# CH4D3M0_Rev_1.net
KiCad netlist of a schematic drawn in EAGLE
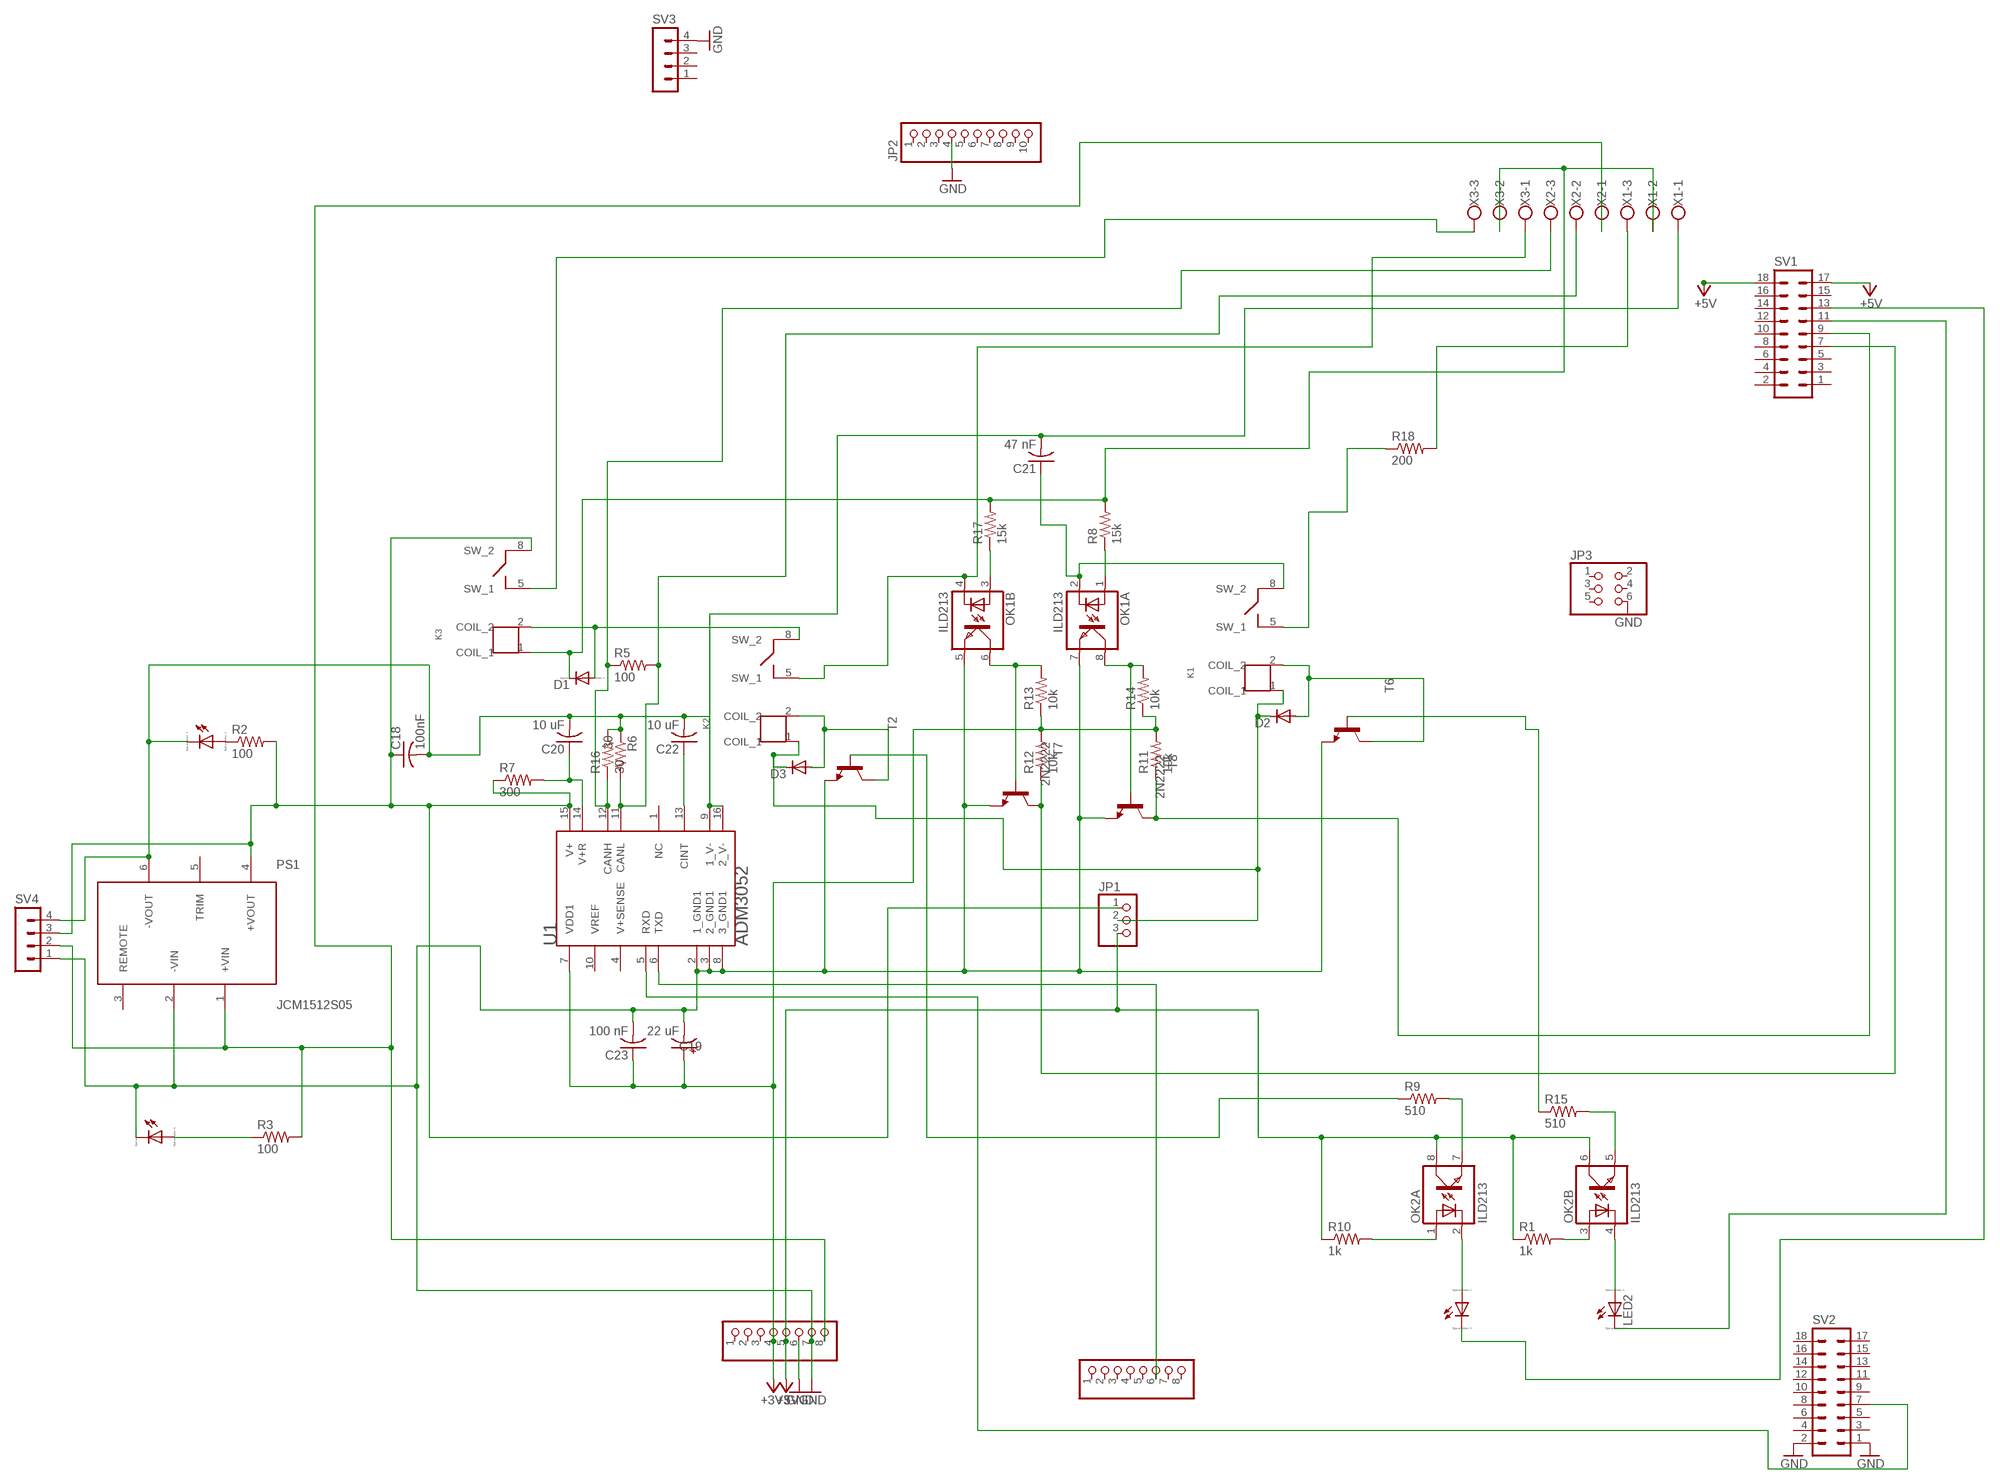
[diagram p0: schematic, sheet 1]

(export (version "E")
  (design (tool "Eeschema 10.0.6"))
  (components
    (comp (ref "ADCH")
      (value "PINHD-1X8")
      (footprint "eagle-import:1X08")
      (libsource (lib "eagle-import") (part "PINHD-1X8"))
    )
    (comp (ref "ADCH2")
      (value "PINHD-1X8")
      (footprint "eagle-import:1X08")
      (libsource (lib "eagle-import") (part "PINHD-1X8"))
    )
    (comp (ref "C18")
      (value "100nF")
      (footprint "eagle-import:C025-024X044")
      (libsource (lib "eagle-import") (part "C-US025-024X044"))
    )
    (comp (ref "C19")
      (value "22 uF")
      (footprint "eagle-import:E2,5RE")
      (libsource (lib "eagle-import") (part "CPOL-USE2.5-4V"))
    )
    (comp (ref "C20")
      (value "10 uF")
      (footprint "eagle-import:C025-024X044")
      (libsource (lib "eagle-import") (part "C-US025-024X044"))
    )
    (comp (ref "C21")
      (value "47 nF")
      (footprint "eagle-import:C025-024X044")
      (libsource (lib "eagle-import") (part "C-US025-024X044"))
    )
    (comp (ref "C22")
      (value "10 uF")
      (footprint "eagle-import:C025-024X044")
      (libsource (lib "eagle-import") (part "C-US025-024X044"))
    )
    (comp (ref "C23")
      (value "100 nF")
      (footprint "eagle-import:C025-024X044")
      (libsource (lib "eagle-import") (part "C-US025-024X044"))
    )
    (comp (ref "D1")
      (value "DIODE-D-5")
      (footprint "eagle-import:D-5")
      (libsource (lib "eagle-import") (part "DIODE-D-5"))
    )
    (comp (ref "D2")
      (value "DIODE-D-5")
      (footprint "eagle-import:D-5")
      (libsource (lib "eagle-import") (part "DIODE-D-5"))
    )
    (comp (ref "D3")
      (value "DIODE-D-5")
      (footprint "eagle-import:D-5")
      (libsource (lib "eagle-import") (part "DIODE-D-5"))
    )
    (comp (ref "JP1")
      (value "PINHD-1X3")
      (footprint "eagle-import:1X03")
      (libsource (lib "eagle-import") (part "PINHD-1X3"))
    )
    (comp (ref "JP2")
      (value "PINHD-1X10")
      (footprint "eagle-import:1X10")
      (libsource (lib "eagle-import") (part "PINHD-1X10"))
    )
    (comp (ref "JP3")
      (value "PINHD-2X3")
      (footprint "eagle-import:2X03")
      (libsource (lib "eagle-import") (part "PINHD-2X3"))
    )
    (comp (ref "K1")
      (value "G6DN-1ATHROUGH_HOLE")
      (footprint "eagle-import:G6DN-1A")
      (libsource (lib "eagle-import") (part "G6DN-1ATHROUGH_HOLE"))
    )
    (comp (ref "K2")
      (value "G6DN-1ATHROUGH_HOLE")
      (footprint "eagle-import:G6DN-1A")
      (libsource (lib "eagle-import") (part "G6DN-1ATHROUGH_HOLE"))
    )
    (comp (ref "K3")
      (value "G6DN-1ATHROUGH_HOLE")
      (footprint "eagle-import:G6DN-1A")
      (libsource (lib "eagle-import") (part "G6DN-1ATHROUGH_HOLE"))
    )
    (comp (ref "LED1")
      (value "LED_ELD260")
      (footprint "eagle-import:LED_LD260")
      (libsource (lib "eagle-import") (part "LED_ELD260"))
    )
    (comp (ref "LED2")
      (value "LED_ELD260")
      (footprint "eagle-import:LED_LD260")
      (libsource (lib "eagle-import") (part "LED_ELD260"))
    )
    (comp (ref "LED3")
      (value "LED_ELD260")
      (footprint "eagle-import:LED_LD260")
      (libsource (lib "eagle-import") (part "LED_ELD260"))
    )
    (comp (ref "LED4")
      (value "LED_ELD260")
      (footprint "eagle-import:LED_LD260")
      (libsource (lib "eagle-import") (part "LED_ELD260"))
    )
    (comp (ref "OK1")
      (value "ILD213")
      (footprint "eagle-import:SOIC08")
      (fields (field (name "MF") "VISHAY/TELEFUNKEN") (field (name "MPN") "ILD213T"))
      (libsource (lib "eagle-import") (part "ILD213"))
    )
    (comp (ref "OK2")
      (value "ILD213")
      (footprint "eagle-import:SOIC08")
      (fields (field (name "MF") "VISHAY/TELEFUNKEN") (field (name "MPN") "ILD213T"))
      (libsource (lib "eagle-import") (part "ILD213"))
    )
    (comp (ref "PS1")
      (value "JCM1512S05")
      (footprint "eagle-import:JCMXX")
      (libsource (lib "eagle-import") (part "JCMXXTHROUGH_HOLE"))
    )
    (comp (ref "R1")
      (value "1k")
      (footprint "eagle-import:0204_7")
      (libsource (lib "eagle-import") (part "R-US_0204/7"))
    )
    (comp (ref "R2")
      (value "100")
      (footprint "eagle-import:0204_7")
      (libsource (lib "eagle-import") (part "R-US_0204/7"))
    )
    (comp (ref "R3")
      (value "100")
      (footprint "eagle-import:0204_7")
      (libsource (lib "eagle-import") (part "R-US_0204/7"))
    )
    (comp (ref "R5")
      (value "100")
      (footprint "eagle-import:0204_7")
      (libsource (lib "eagle-import") (part "R-US_0204/7"))
    )
    (comp (ref "R6")
      (value "30")
      (footprint "eagle-import:0204_7")
      (libsource (lib "eagle-import") (part "R-US_0204/7"))
    )
    (comp (ref "R7")
      (value "300")
      (footprint "eagle-import:0204_7")
      (libsource (lib "eagle-import") (part "R-US_0204/7"))
    )
    (comp (ref "R8")
      (value "15k")
      (footprint "eagle-import:0204_7")
      (libsource (lib "eagle-import") (part "R-US_0204/7"))
    )
    (comp (ref "R9")
      (value "510")
      (footprint "eagle-import:0204_7")
      (libsource (lib "eagle-import") (part "R-US_0204/7"))
    )
    (comp (ref "R10")
      (value "1k")
      (footprint "eagle-import:0204_7")
      (libsource (lib "eagle-import") (part "R-US_0204/7"))
    )
    (comp (ref "R11")
      (value "10k")
      (footprint "eagle-import:0204_7")
      (libsource (lib "eagle-import") (part "R-US_0204/7"))
    )
    (comp (ref "R12")
      (value "10k")
      (footprint "eagle-import:0204_7")
      (libsource (lib "eagle-import") (part "R-US_0204/7"))
    )
    (comp (ref "R13")
      (value "10k")
      (footprint "eagle-import:0204_7")
      (libsource (lib "eagle-import") (part "R-US_0204/7"))
    )
    (comp (ref "R14")
      (value "10k")
      (footprint "eagle-import:0204_7")
      (libsource (lib "eagle-import") (part "R-US_0204/7"))
    )
    (comp (ref "R15")
      (value "510")
      (footprint "eagle-import:0204_7")
      (libsource (lib "eagle-import") (part "R-US_0204/7"))
    )
    (comp (ref "R16")
      (value "30")
      (footprint "eagle-import:0204_7")
      (libsource (lib "eagle-import") (part "R-US_0204/7"))
    )
    (comp (ref "R17")
      (value "15k")
      (footprint "eagle-import:0204_7")
      (libsource (lib "eagle-import") (part "R-US_0204/7"))
    )
    (comp (ref "R18")
      (value "200")
      (footprint "eagle-import:0204_7")
      (libsource (lib "eagle-import") (part "R-US_0204/7"))
    )
    (comp (ref "SV1")
      (value "MA09-2")
      (footprint "eagle-import:MA09-2")
      (libsource (lib "eagle-import") (part "MA09-2"))
    )
    (comp (ref "SV2")
      (value "MA09-2")
      (footprint "eagle-import:MA09-2")
      (libsource (lib "eagle-import") (part "MA09-2"))
    )
    (comp (ref "SV3")
      (value "MA04-1")
      (footprint "eagle-import:MA04-1")
      (libsource (lib "eagle-import") (part "MA04-1"))
    )
    (comp (ref "SV4")
      (value "MA04-1")
      (footprint "eagle-import:MA04-1")
      (libsource (lib "eagle-import") (part "MA04-1"))
    )
    (comp (ref "T2")
      (value "BC547-NPN-TO92-CBE")
      (footprint "eagle-import:TO92-CBE")
      (libsource (lib "eagle-import") (part "-NPN-TO92-CBEBC547"))
    )
    (comp (ref "T6")
      (value "BC547-NPN-TO92-CBE")
      (footprint "eagle-import:TO92-CBE")
      (libsource (lib "eagle-import") (part "-NPN-TO92-CBEBC547"))
    )
    (comp (ref "T7")
      (value "2N2222")
      (footprint "eagle-import:TO92-EBC-OVAL")
      (libsource (lib "eagle-import") (part "2N2222"))
    )
    (comp (ref "T8")
      (value "2N2222")
      (footprint "eagle-import:TO92-EBC-OVAL")
      (libsource (lib "eagle-import") (part "2N2222"))
    )
    (comp (ref "U1")
      (value "ANALOG_DEVICES_INC_ADM3052ANALOG_DEVICES_INC_ADM3052_0_0")
      (footprint "eagle-import:ANALOG_DEVICES_INC_ADM3052_0")
      (fields
        (field (name "DIGIKEY_PART_NUMBER") "ADM3052BRWZ-REEL7")
        (field (name "MF") "Analog Devices Inc")
        (field (name "MOUSER_PART_NUMBER") "584-ADM3052BRWZ-R7")
      )
      (libsource (lib "eagle-import") (part "ANALOG_DEVICES_INC_ADM3052ANALOG_DEVICES_INC_ADM3052_0_0"))
    )
    (comp (ref "X1")
      (value "W237-103")
      (footprint "eagle-import:W237-103")
      (fields (field (name "MPN") "237-103"))
      (libsource (lib "eagle-import") (part "W237-103"))
    )
    (comp (ref "X2")
      (value "W237-103")
      (footprint "eagle-import:W237-103")
      (fields (field (name "MPN") "237-103"))
      (libsource (lib "eagle-import") (part "W237-103"))
    )
    (comp (ref "X3")
      (value "W237-103")
      (footprint "eagle-import:W237-103")
      (fields (field (name "MPN") "237-103"))
      (libsource (lib "eagle-import") (part "W237-103"))
    )
  )
  (nets
    (net (code "1") (name "+3V3") (class "Default")
      (node (ref "ADCH2") (pin "4") (pinfunction "4_4") (pintype "passive"))
      (node (ref "C19") (pin "+") (pinfunction "+_+") (pintype "passive"))
      (node (ref "C23") (pin "1") (pinfunction "1_1") (pintype "passive"))
      (node (ref "R11") (pin "2") (pinfunction "2_2") (pintype "passive"))
      (node (ref "R12") (pin "2") (pinfunction "2_2") (pintype "passive"))
      (node (ref "R13") (pin "1") (pinfunction "1_1") (pintype "passive"))
      (node (ref "R14") (pin "1") (pinfunction "1_1") (pintype "passive"))
      (node (ref "U1") (pin "7") (pinfunction "VDD1_7") (pintype "bidirectional"))
    )
    (net (code "2") (name "+5V") (class "Default")
      (node (ref "ADCH2") (pin "5") (pinfunction "5_5") (pintype "passive"))
      (node (ref "JP1") (pin "3") (pinfunction "3_3") (pintype "passive"))
      (node (ref "OK2") (pin "6") (pinfunction "COL_6") (pintype "passive"))
      (node (ref "OK2") (pin "8") (pinfunction "COL_8") (pintype "passive"))
      (node (ref "R1") (pin "1") (pinfunction "1_1") (pintype "passive"))
      (node (ref "R10") (pin "1") (pinfunction "1_1") (pintype "passive"))
      (node (ref "SV1") (pin "17") (pinfunction "17_17") (pintype "passive"))
      (node (ref "SV1") (pin "18") (pinfunction "18_18") (pintype "passive"))
    )
    (net (code "3") (name "GND") (class "Default")
      (node (ref "ADCH2") (pin "6") (pinfunction "6_6") (pintype "passive"))
      (node (ref "ADCH2") (pin "7") (pinfunction "7_7") (pintype "passive"))
      (node (ref "C19") (pin "-") (pinfunction "-_-") (pintype "passive"))
      (node (ref "C23") (pin "2") (pinfunction "2_2") (pintype "passive"))
      (node (ref "JP2") (pin "4") (pinfunction "4_4") (pintype "passive"))
      (node (ref "JP3") (pin "6") (pinfunction "6_6") (pintype "passive"))
      (node (ref "LED4") (pin "K") (pinfunction "C_K") (pintype "passive"))
      (node (ref "OK1") (pin "5") (pinfunction "EMIT_5") (pintype "passive"))
      (node (ref "OK1") (pin "7") (pinfunction "EMIT_7") (pintype "passive"))
      (node (ref "PS1") (pin "2") (pinfunction "-VIN_2") (pintype "power_in"))
      (node (ref "SV2") (pin "1") (pinfunction "1_1") (pintype "passive"))
      (node (ref "SV2") (pin "2") (pinfunction "2_2") (pintype "passive"))
      (node (ref "SV3") (pin "4") (pinfunction "4_4") (pintype "passive"))
      (node (ref "SV4") (pin "1") (pinfunction "1_1") (pintype "passive"))
      (node (ref "T2") (pin "E") (pinfunction "E_E") (pintype "passive"))
      (node (ref "T6") (pin "E") (pinfunction "E_E") (pintype "passive"))
      (node (ref "T7") (pin "E") (pinfunction "E_E") (pintype "passive"))
      (node (ref "T8") (pin "E") (pinfunction "E_E") (pintype "passive"))
      (node (ref "U1") (pin "2") (pinfunction "1_GND1_2") (pintype "bidirectional"))
      (node (ref "U1") (pin "3") (pinfunction "2_GND1_3") (pintype "bidirectional"))
      (node (ref "U1") (pin "8") (pinfunction "3_GND1_8") (pintype "bidirectional"))
    )
    (net (code "4") (name "Net-(K1-COIL_1)") (class "Default")
      (node (ref "D2") (pin "C") (pinfunction "C_C") (pintype "passive"))
      (node (ref "D3") (pin "C") (pinfunction "C_C") (pintype "passive"))
      (node (ref "JP1") (pin "2") (pinfunction "2_2") (pintype "passive"))
      (node (ref "K1") (pin "1") (pinfunction "COIL_1_1") (pintype "bidirectional"))
      (node (ref "K2") (pin "1") (pinfunction "COIL_1_1") (pintype "bidirectional"))
    )
    (net (code "5") (name "Net-(K1-COIL_2)") (class "Default")
      (node (ref "D2") (pin "A") (pinfunction "A_A") (pintype "passive"))
      (node (ref "K1") (pin "2") (pinfunction "COIL_2_2") (pintype "bidirectional"))
      (node (ref "T6") (pin "C") (pinfunction "C_C") (pintype "passive"))
    )
    (net (code "6") (name "Net-(K1-SW_1)") (class "Default")
      (node (ref "K1") (pin "5") (pinfunction "SW_1_5") (pintype "bidirectional"))
      (node (ref "R18") (pin "1") (pinfunction "1_1") (pintype "passive"))
    )
    (net (code "7") (name "Net-(K1-SW_2)") (class "Default")
      (node (ref "C21") (pin "1") (pinfunction "1_1") (pintype "passive"))
      (node (ref "K1") (pin "8") (pinfunction "SW_2_8") (pintype "bidirectional"))
      (node (ref "OK1") (pin "2") (pinfunction "C_2") (pintype "passive"))
    )
    (net (code "8") (name "Net-(K2-COIL_2)") (class "Default")
      (node (ref "D3") (pin "A") (pinfunction "A_A") (pintype "passive"))
      (node (ref "K2") (pin "2") (pinfunction "COIL_2_2") (pintype "bidirectional"))
      (node (ref "T2") (pin "C") (pinfunction "C_C") (pintype "passive"))
    )
    (net (code "9") (name "Net-(K2-SW_1)") (class "Default")
      (node (ref "K2") (pin "5") (pinfunction "SW_1_5") (pintype "bidirectional"))
      (node (ref "OK1") (pin "4") (pinfunction "C_4") (pintype "passive"))
      (node (ref "X3") (pin "1") (pinfunction "KL_1") (pintype "passive"))
    )
    (net (code "10") (name "Net-(K2-SW_2)") (class "Default")
      (node (ref "D1") (pin "A") (pinfunction "A_A") (pintype "passive"))
      (node (ref "K2") (pin "8") (pinfunction "SW_2_8") (pintype "bidirectional"))
      (node (ref "K3") (pin "2") (pinfunction "COIL_2_2") (pintype "bidirectional"))
    )
    (net (code "11") (name "Net-(K3-COIL_1)") (class "Default")
      (node (ref "D1") (pin "C") (pinfunction "C_C") (pintype "passive"))
      (node (ref "K3") (pin "1") (pinfunction "COIL_1_1") (pintype "bidirectional"))
      (node (ref "R17") (pin "2") (pinfunction "2_2") (pintype "passive"))
      (node (ref "R8") (pin "2") (pinfunction "2_2") (pintype "passive"))
      (node (ref "X1") (pin "2") (pinfunction "KL_2") (pintype "passive"))
      (node (ref "X3") (pin "2") (pinfunction "KL_2") (pintype "passive"))
    )
    (net (code "12") (name "Net-(K3-SW_1)") (class "Default")
      (node (ref "K3") (pin "5") (pinfunction "SW_1_5") (pintype "bidirectional"))
      (node (ref "X3") (pin "3") (pinfunction "KL_3") (pintype "passive"))
    )
    (net (code "13") (name "Net-(K3-SW_2)") (class "Default")
      (node (ref "C18") (pin "1") (pinfunction "1_1") (pintype "passive"))
      (node (ref "JP1") (pin "1") (pinfunction "1_1") (pintype "passive"))
      (node (ref "K3") (pin "8") (pinfunction "SW_2_8") (pintype "bidirectional"))
      (node (ref "PS1") (pin "4") (pinfunction "+VOUT_4") (pintype "output"))
      (node (ref "R2") (pin "2") (pinfunction "2_2") (pintype "passive"))
      (node (ref "R7") (pin "1") (pinfunction "1_1") (pintype "passive"))
      (node (ref "SV4") (pin "3") (pinfunction "3_3") (pintype "passive"))
      (node (ref "U1") (pin "15") (pinfunction "V+_15") (pintype "bidirectional"))
    )
    (net (code "14") (name "Net-(LED1-C)") (class "Default")
      (node (ref "LED1") (pin "K") (pinfunction "C_K") (pintype "passive"))
      (node (ref "SV1") (pin "13") (pinfunction "13_13") (pintype "passive"))
    )
    (net (code "15") (name "Net-(LED2-C)") (class "Default")
      (node (ref "LED2") (pin "K") (pinfunction "C_K") (pintype "passive"))
      (node (ref "SV1") (pin "11") (pinfunction "11_11") (pintype "passive"))
    )
    (net (code "16") (name "Net-(LED3-C)") (class "Default")
      (node (ref "C18") (pin "2") (pinfunction "2_2") (pintype "passive"))
      (node (ref "C20") (pin "2") (pinfunction "2_2") (pintype "passive"))
      (node (ref "C21") (pin "2") (pinfunction "2_2") (pintype "passive"))
      (node (ref "C22") (pin "2") (pinfunction "2_2") (pintype "passive"))
      (node (ref "LED3") (pin "K") (pinfunction "C_K") (pintype "passive"))
      (node (ref "PS1") (pin "6") (pinfunction "-VOUT_6") (pintype "output"))
      (node (ref "R16") (pin "2") (pinfunction "2_2") (pintype "passive"))
      (node (ref "R6") (pin "1") (pinfunction "1_1") (pintype "passive"))
      (node (ref "SV4") (pin "4") (pinfunction "4_4") (pintype "passive"))
      (node (ref "U1") (pin "16") (pinfunction "2_V-_16") (pintype "bidirectional"))
      (node (ref "U1") (pin "9") (pinfunction "1_V-_9") (pintype "bidirectional"))
      (node (ref "X1") (pin "1") (pinfunction "KL_1") (pintype "passive"))
    )
    (net (code "17") (name "Net-(LED3-PadA)") (class "Default")
      (node (ref "LED3") (pin "A") (pinfunction "A_A") (pintype "passive"))
      (node (ref "R2") (pin "1") (pinfunction "1_1") (pintype "passive"))
    )
    (net (code "18") (name "Net-(LED4-PadA)") (class "Default")
      (node (ref "LED4") (pin "A") (pinfunction "A_A") (pintype "passive"))
      (node (ref "R3") (pin "1") (pinfunction "1_1") (pintype "passive"))
    )
    (net (code "19") (name "Net-(OK1A-A)") (class "Default")
      (node (ref "OK1") (pin "1") (pinfunction "A_1") (pintype "passive"))
      (node (ref "R8") (pin "1") (pinfunction "1_1") (pintype "passive"))
    )
    (net (code "20") (name "Net-(OK1A-COL)") (class "Default")
      (node (ref "OK1") (pin "8") (pinfunction "COL_8") (pintype "passive"))
      (node (ref "R14") (pin "2") (pinfunction "2_2") (pintype "passive"))
      (node (ref "T8") (pin "B") (pinfunction "B_B") (pintype "passive"))
    )
    (net (code "21") (name "Net-(OK1B-A)") (class "Default")
      (node (ref "OK1") (pin "3") (pinfunction "A_3") (pintype "passive"))
      (node (ref "R17") (pin "1") (pinfunction "1_1") (pintype "passive"))
    )
    (net (code "22") (name "Net-(OK1B-COL)") (class "Default")
      (node (ref "OK1") (pin "6") (pinfunction "COL_6") (pintype "passive"))
      (node (ref "R13") (pin "2") (pinfunction "2_2") (pintype "passive"))
      (node (ref "T7") (pin "B") (pinfunction "B_B") (pintype "passive"))
    )
    (net (code "23") (name "Net-(OK2A-A)") (class "Default")
      (node (ref "OK2") (pin "1") (pinfunction "A_1") (pintype "passive"))
      (node (ref "R10") (pin "2") (pinfunction "2_2") (pintype "passive"))
    )
    (net (code "24") (name "Net-(OK2A-C)") (class "Default")
      (node (ref "LED1") (pin "A") (pinfunction "A_A") (pintype "passive"))
      (node (ref "OK2") (pin "2") (pinfunction "C_2") (pintype "passive"))
    )
    (net (code "25") (name "Net-(OK2A-EMIT)") (class "Default")
      (node (ref "OK2") (pin "7") (pinfunction "EMIT_7") (pintype "passive"))
      (node (ref "R9") (pin "2") (pinfunction "2_2") (pintype "passive"))
    )
    (net (code "26") (name "Net-(OK2B-A)") (class "Default")
      (node (ref "OK2") (pin "3") (pinfunction "A_3") (pintype "passive"))
      (node (ref "R1") (pin "2") (pinfunction "2_2") (pintype "passive"))
    )
    (net (code "27") (name "Net-(OK2B-C)") (class "Default")
      (node (ref "LED2") (pin "A") (pinfunction "A_A") (pintype "passive"))
      (node (ref "OK2") (pin "4") (pinfunction "C_4") (pintype "passive"))
    )
    (net (code "28") (name "Net-(OK2B-EMIT)") (class "Default")
      (node (ref "OK2") (pin "5") (pinfunction "EMIT_5") (pintype "passive"))
      (node (ref "R15") (pin "2") (pinfunction "2_2") (pintype "passive"))
    )
    (net (code "29") (name "Net-(PS1-+VIN)") (class "Default")
      (node (ref "ADCH2") (pin "8") (pinfunction "8_8") (pintype "passive"))
      (node (ref "PS1") (pin "1") (pinfunction "+VIN_1") (pintype "power_in"))
      (node (ref "R3") (pin "2") (pinfunction "2_2") (pintype "passive"))
      (node (ref "SV4") (pin "2") (pinfunction "2_2") (pintype "passive"))
      (node (ref "X2") (pin "1") (pinfunction "KL_1") (pintype "passive"))
    )
    (net (code "30") (name "Net-(R9-Pad1)") (class "Default")
      (node (ref "R9") (pin "1") (pinfunction "1_1") (pintype "passive"))
      (node (ref "T2") (pin "B") (pinfunction "B_B") (pintype "passive"))
    )
    (net (code "31") (name "Net-(R11-Pad1)") (class "Default")
      (node (ref "R11") (pin "1") (pinfunction "1_1") (pintype "passive"))
      (node (ref "SV1") (pin "9") (pinfunction "9_9") (pintype "passive"))
      (node (ref "T8") (pin "C") (pinfunction "C_C") (pintype "passive"))
    )
    (net (code "32") (name "Net-(R12-Pad1)") (class "Default")
      (node (ref "R12") (pin "1") (pinfunction "1_1") (pintype "passive"))
      (node (ref "SV1") (pin "7") (pinfunction "7_7") (pintype "passive"))
      (node (ref "T7") (pin "C") (pinfunction "C_C") (pintype "passive"))
    )
    (net (code "33") (name "Net-(R15-Pad1)") (class "Default")
      (node (ref "R15") (pin "1") (pinfunction "1_1") (pintype "passive"))
      (node (ref "T6") (pin "B") (pinfunction "B_B") (pintype "passive"))
    )
    (net (code "34") (name "Net-(U1-CANH)") (class "Default")
      (node (ref "R16") (pin "1") (pinfunction "1_1") (pintype "passive"))
      (node (ref "R5") (pin "1") (pinfunction "1_1") (pintype "passive"))
      (node (ref "U1") (pin "12") (pinfunction "CANH_12") (pintype "bidirectional"))
      (node (ref "X2") (pin "3") (pinfunction "KL_3") (pintype "passive"))
    )
    (net (code "35") (name "Net-(U1-CANL)") (class "Default")
      (node (ref "R5") (pin "2") (pinfunction "2_2") (pintype "passive"))
      (node (ref "R6") (pin "2") (pinfunction "2_2") (pintype "passive"))
      (node (ref "U1") (pin "11") (pinfunction "CANL_11") (pintype "bidirectional"))
      (node (ref "X2") (pin "2") (pinfunction "KL_2") (pintype "passive"))
    )
    (net (code "36") (name "Net-(U1-CINT)") (class "Default")
      (node (ref "C22") (pin "1") (pinfunction "1_1") (pintype "passive"))
      (node (ref "U1") (pin "13") (pinfunction "CINT_13") (pintype "bidirectional"))
    )
    (net (code "37") (name "Net-(U1-RXD)") (class "Default")
      (node (ref "SV2") (pin "7") (pinfunction "7_7") (pintype "passive"))
      (node (ref "U1") (pin "5") (pinfunction "RXD_5") (pintype "bidirectional"))
    )
    (net (code "38") (name "Net-(U1-TXD)") (class "Default")
      (node (ref "ADCH") (pin "6") (pinfunction "6_6") (pintype "passive"))
      (node (ref "U1") (pin "6") (pinfunction "TXD_6") (pintype "bidirectional"))
    )
    (net (code "39") (name "Net-(U1-V+R)") (class "Default")
      (node (ref "C20") (pin "1") (pinfunction "1_1") (pintype "passive"))
      (node (ref "R7") (pin "2") (pinfunction "2_2") (pintype "passive"))
      (node (ref "U1") (pin "14") (pinfunction "V+R_14") (pintype "bidirectional"))
    )
    (net (code "40") (name "Net-(X1C-KL)") (class "Default")
      (node (ref "R18") (pin "2") (pinfunction "2_2") (pintype "passive"))
      (node (ref "X1") (pin "3") (pinfunction "KL_3") (pintype "passive"))
    )
    (net (code "41") (name "unconnected-(ADCH-Pad1)") (class "Default")
      (node (ref "ADCH") (pin "1") (pinfunction "1_1") (pintype "passive"))
    )
    (net (code "42") (name "unconnected-(ADCH-Pad2)") (class "Default")
      (node (ref "ADCH") (pin "2") (pinfunction "2_2") (pintype "passive"))
    )
    (net (code "43") (name "unconnected-(ADCH-Pad3)") (class "Default")
      (node (ref "ADCH") (pin "3") (pinfunction "3_3") (pintype "passive"))
    )
    (net (code "44") (name "unconnected-(ADCH-Pad4)") (class "Default")
      (node (ref "ADCH") (pin "4") (pinfunction "4_4") (pintype "passive"))
    )
    (net (code "45") (name "unconnected-(ADCH-Pad5)") (class "Default")
      (node (ref "ADCH") (pin "5") (pinfunction "5_5") (pintype "passive"))
    )
    (net (code "46") (name "unconnected-(ADCH-Pad7)") (class "Default")
      (node (ref "ADCH") (pin "7") (pinfunction "7_7") (pintype "passive"))
    )
    (net (code "47") (name "unconnected-(ADCH-Pad8)") (class "Default")
      (node (ref "ADCH") (pin "8") (pinfunction "8_8") (pintype "passive"))
    )
    (net (code "48") (name "unconnected-(ADCH2-Pad1)") (class "Default")
      (node (ref "ADCH2") (pin "1") (pinfunction "1_1") (pintype "passive"))
    )
    (net (code "49") (name "unconnected-(ADCH2-Pad2)") (class "Default")
      (node (ref "ADCH2") (pin "2") (pinfunction "2_2") (pintype "passive"))
    )
    (net (code "50") (name "unconnected-(ADCH2-Pad3)") (class "Default")
      (node (ref "ADCH2") (pin "3") (pinfunction "3_3") (pintype "passive"))
    )
    (net (code "51") (name "unconnected-(JP2-Pad1)") (class "Default")
      (node (ref "JP2") (pin "1") (pinfunction "1_1") (pintype "passive"))
    )
    (net (code "52") (name "unconnected-(JP2-Pad2)") (class "Default")
      (node (ref "JP2") (pin "2") (pinfunction "2_2") (pintype "passive"))
    )
    (net (code "53") (name "unconnected-(JP2-Pad3)") (class "Default")
      (node (ref "JP2") (pin "3") (pinfunction "3_3") (pintype "passive"))
    )
    (net (code "54") (name "unconnected-(JP2-Pad5)") (class "Default")
      (node (ref "JP2") (pin "5") (pinfunction "5_5") (pintype "passive"))
    )
    (net (code "55") (name "unconnected-(JP2-Pad6)") (class "Default")
      (node (ref "JP2") (pin "6") (pinfunction "6_6") (pintype "passive"))
    )
    (net (code "56") (name "unconnected-(JP2-Pad7)") (class "Default")
      (node (ref "JP2") (pin "7") (pinfunction "7_7") (pintype "passive"))
    )
    (net (code "57") (name "unconnected-(JP2-Pad8)") (class "Default")
      (node (ref "JP2") (pin "8") (pinfunction "8_8") (pintype "passive"))
    )
    (net (code "58") (name "unconnected-(JP2-Pad9)") (class "Default")
      (node (ref "JP2") (pin "9") (pinfunction "9_9") (pintype "passive"))
    )
    (net (code "59") (name "unconnected-(JP2-Pad10)") (class "Default")
      (node (ref "JP2") (pin "10") (pinfunction "10_10") (pintype "passive"))
    )
    (net (code "60") (name "unconnected-(JP3-Pad1)") (class "Default")
      (node (ref "JP3") (pin "1") (pinfunction "1_1") (pintype "passive"))
    )
    (net (code "61") (name "unconnected-(JP3-Pad2)") (class "Default")
      (node (ref "JP3") (pin "2") (pinfunction "2_2") (pintype "passive"))
    )
    (net (code "62") (name "unconnected-(JP3-Pad3)") (class "Default")
      (node (ref "JP3") (pin "3") (pinfunction "3_3") (pintype "passive"))
    )
    (net (code "63") (name "unconnected-(JP3-Pad4)") (class "Default")
      (node (ref "JP3") (pin "4") (pinfunction "4_4") (pintype "passive"))
    )
    (net (code "64") (name "unconnected-(JP3-Pad5)") (class "Default")
      (node (ref "JP3") (pin "5") (pinfunction "5_5") (pintype "passive"))
    )
    (net (code "65") (name "unconnected-(PS1-REMOTE-Pad3)") (class "Default")
      (node (ref "PS1") (pin "3") (pinfunction "REMOTE_3") (pintype "input"))
    )
    (net (code "66") (name "unconnected-(PS1-TRIM-Pad5)") (class "Default")
      (node (ref "PS1") (pin "5") (pinfunction "TRIM_5") (pintype "input"))
    )
    (net (code "67") (name "unconnected-(SV1-Pad1)") (class "Default")
      (node (ref "SV1") (pin "1") (pinfunction "1_1") (pintype "passive"))
    )
    (net (code "68") (name "unconnected-(SV1-Pad2)") (class "Default")
      (node (ref "SV1") (pin "2") (pinfunction "2_2") (pintype "passive"))
    )
    (net (code "69") (name "unconnected-(SV1-Pad3)") (class "Default")
      (node (ref "SV1") (pin "3") (pinfunction "3_3") (pintype "passive"))
    )
    (net (code "70") (name "unconnected-(SV1-Pad4)") (class "Default")
      (node (ref "SV1") (pin "4") (pinfunction "4_4") (pintype "passive"))
    )
    (net (code "71") (name "unconnected-(SV1-Pad5)") (class "Default")
      (node (ref "SV1") (pin "5") (pinfunction "5_5") (pintype "passive"))
    )
    (net (code "72") (name "unconnected-(SV1-Pad6)") (class "Default")
      (node (ref "SV1") (pin "6") (pinfunction "6_6") (pintype "passive"))
    )
    (net (code "73") (name "unconnected-(SV1-Pad8)") (class "Default")
      (node (ref "SV1") (pin "8") (pinfunction "8_8") (pintype "passive"))
    )
    (net (code "74") (name "unconnected-(SV1-Pad10)") (class "Default")
      (node (ref "SV1") (pin "10") (pinfunction "10_10") (pintype "passive"))
    )
    (net (code "75") (name "unconnected-(SV1-Pad12)") (class "Default")
      (node (ref "SV1") (pin "12") (pinfunction "12_12") (pintype "passive"))
    )
    (net (code "76") (name "unconnected-(SV1-Pad14)") (class "Default")
      (node (ref "SV1") (pin "14") (pinfunction "14_14") (pintype "passive"))
    )
    (net (code "77") (name "unconnected-(SV1-Pad15)") (class "Default")
      (node (ref "SV1") (pin "15") (pinfunction "15_15") (pintype "passive"))
    )
    (net (code "78") (name "unconnected-(SV1-Pad16)") (class "Default")
      (node (ref "SV1") (pin "16") (pinfunction "16_16") (pintype "passive"))
    )
    (net (code "79") (name "unconnected-(SV2-Pad3)") (class "Default")
      (node (ref "SV2") (pin "3") (pinfunction "3_3") (pintype "passive"))
    )
    (net (code "80") (name "unconnected-(SV2-Pad4)") (class "Default")
      (node (ref "SV2") (pin "4") (pinfunction "4_4") (pintype "passive"))
    )
    (net (code "81") (name "unconnected-(SV2-Pad5)") (class "Default")
      (node (ref "SV2") (pin "5") (pinfunction "5_5") (pintype "passive"))
    )
    (net (code "82") (name "unconnected-(SV2-Pad6)") (class "Default")
      (node (ref "SV2") (pin "6") (pinfunction "6_6") (pintype "passive"))
    )
    (net (code "83") (name "unconnected-(SV2-Pad8)") (class "Default")
      (node (ref "SV2") (pin "8") (pinfunction "8_8") (pintype "passive"))
    )
    (net (code "84") (name "unconnected-(SV2-Pad9)") (class "Default")
      (node (ref "SV2") (pin "9") (pinfunction "9_9") (pintype "passive"))
    )
    (net (code "85") (name "unconnected-(SV2-Pad10)") (class "Default")
      (node (ref "SV2") (pin "10") (pinfunction "10_10") (pintype "passive"))
    )
    (net (code "86") (name "unconnected-(SV2-Pad11)") (class "Default")
      (node (ref "SV2") (pin "11") (pinfunction "11_11") (pintype "passive"))
    )
    (net (code "87") (name "unconnected-(SV2-Pad12)") (class "Default")
      (node (ref "SV2") (pin "12") (pinfunction "12_12") (pintype "passive"))
    )
    (net (code "88") (name "unconnected-(SV2-Pad13)") (class "Default")
      (node (ref "SV2") (pin "13") (pinfunction "13_13") (pintype "passive"))
    )
    (net (code "89") (name "unconnected-(SV2-Pad14)") (class "Default")
      (node (ref "SV2") (pin "14") (pinfunction "14_14") (pintype "passive"))
    )
    (net (code "90") (name "unconnected-(SV2-Pad15)") (class "Default")
      (node (ref "SV2") (pin "15") (pinfunction "15_15") (pintype "passive"))
    )
    (net (code "91") (name "unconnected-(SV2-Pad16)") (class "Default")
      (node (ref "SV2") (pin "16") (pinfunction "16_16") (pintype "passive"))
    )
    (net (code "92") (name "unconnected-(SV2-Pad17)") (class "Default")
      (node (ref "SV2") (pin "17") (pinfunction "17_17") (pintype "passive"))
    )
    (net (code "93") (name "unconnected-(SV2-Pad18)") (class "Default")
      (node (ref "SV2") (pin "18") (pinfunction "18_18") (pintype "passive"))
    )
    (net (code "94") (name "unconnected-(SV3-Pad1)") (class "Default")
      (node (ref "SV3") (pin "1") (pinfunction "1_1") (pintype "passive"))
    )
    (net (code "95") (name "unconnected-(SV3-Pad2)") (class "Default")
      (node (ref "SV3") (pin "2") (pinfunction "2_2") (pintype "passive"))
    )
    (net (code "96") (name "unconnected-(SV3-Pad3)") (class "Default")
      (node (ref "SV3") (pin "3") (pinfunction "3_3") (pintype "passive"))
    )
    (net (code "97") (name "unconnected-(U1-NC-Pad1)") (class "Default")
      (node (ref "U1") (pin "1") (pinfunction "NC_1") (pintype "bidirectional"))
    )
    (net (code "98") (name "unconnected-(U1-V+SENSE-Pad4)") (class "Default")
      (node (ref "U1") (pin "4") (pinfunction "V+SENSE_4") (pintype "bidirectional"))
    )
    (net (code "99") (name "unconnected-(U1-VREF-Pad10)") (class "Default")
      (node (ref "U1") (pin "10") (pinfunction "VREF_10") (pintype "bidirectional"))
    )
  )
)
